# Power.net
KiCad netlist of a schematic drawn in Altium Designer
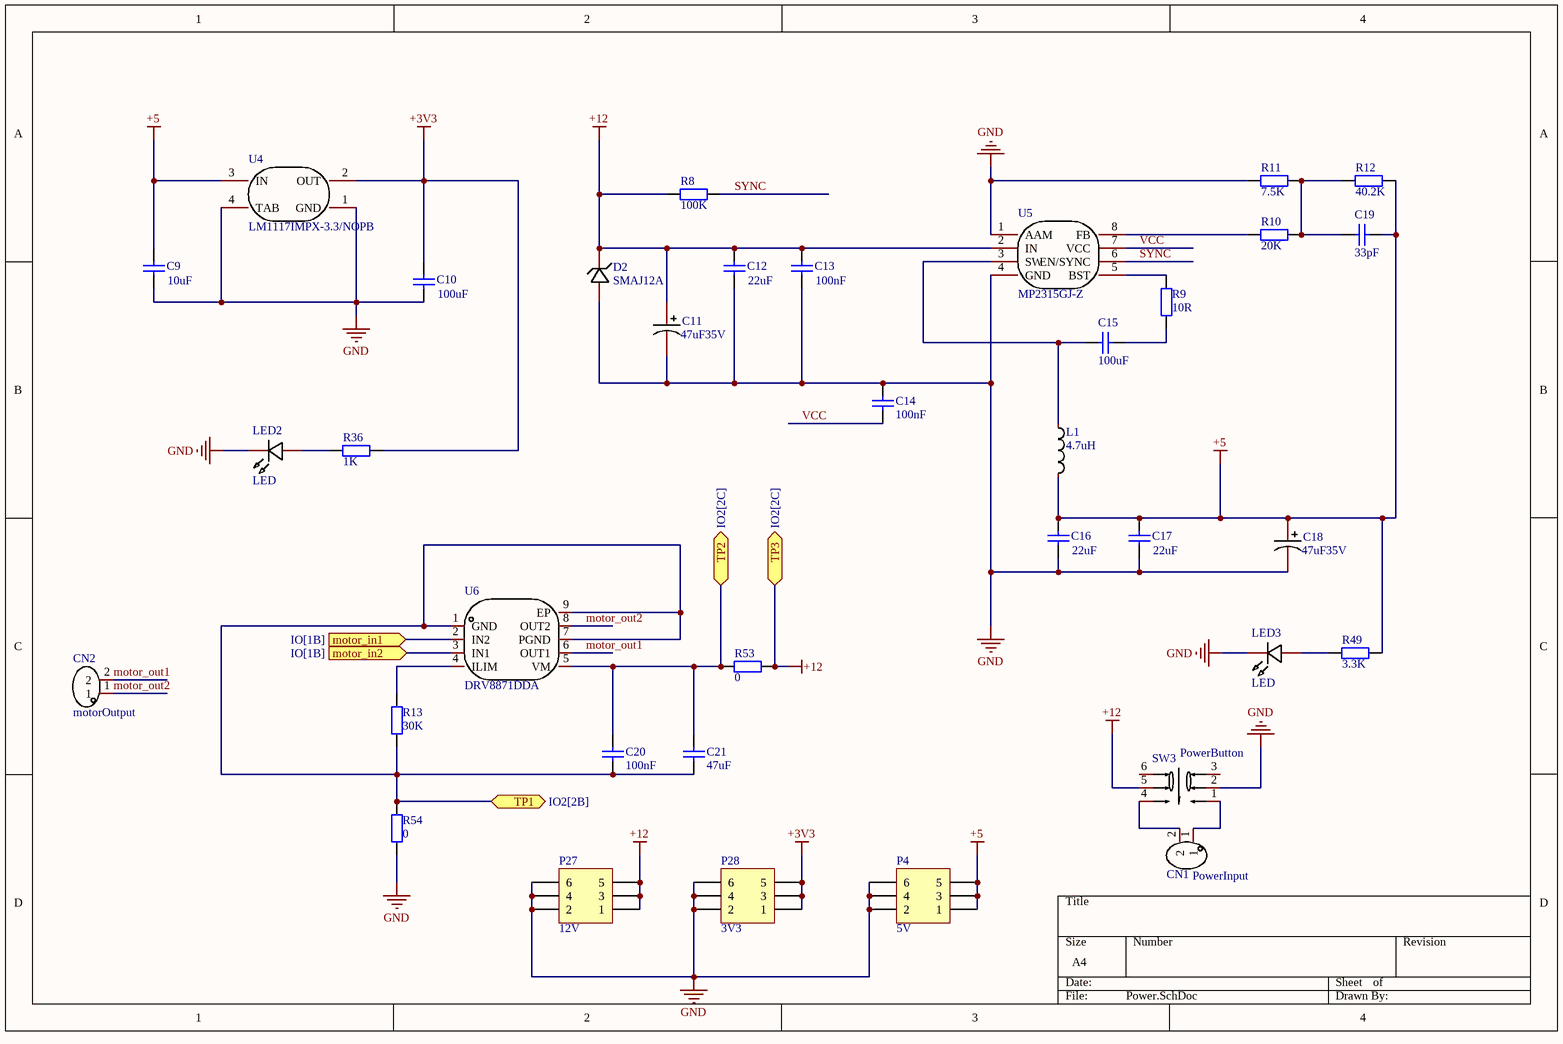
[diagram p0: Power.SchDoc]

(export (version "E")
  (design (tool "Eeschema 10.0.6"))
  (components
    (comp (ref "C9")
      (value "10uF")
      (footprint "RAD-0.3")
      (description "Capacitor")
      (fields (field (name "Comment") "Cap") (field (name "PUBLISHER") "Altium Limited"))
      (libsource (lib "Miscellaneous Devices") (part "Cap"))
    )
    (comp (ref "C10")
      (value "100uF")
      (footprint "RAD-0.3")
      (description "Capacitor")
      (fields (field (name "Comment") "Cap") (field (name "PUBLISHER") "Altium Limited"))
      (libsource (lib "Miscellaneous Devices") (part "Cap"))
    )
    (comp (ref "C11")
      (value "47uF")
      (footprint "CAP-TH_BD5.0-P2.00-D0.5-FD-A")
      (fields
        (field (name "MANUFACTURER") "KNSCHA(科尼盛)")
        (field (name "MANUFACTURER PART") "01EC1119")
        (field (name "TOLERANCE") "±20%")
        (field (name "NAME") "47uF35V")
      )
      (libsource (lib "47uF35V") (part "01EC1119"))
    )
    (comp (ref "C12")
      (value "22uF")
      (footprint "RAD-0.3")
      (description "Capacitor")
      (fields (field (name "Comment") "Cap") (field (name "PUBLISHER") "Altium Limited"))
      (libsource (lib "Miscellaneous Devices") (part "Cap"))
    )
    (comp (ref "C13")
      (value "100nF")
      (footprint "RAD-0.3")
      (description "Capacitor")
      (fields (field (name "Comment") "Cap") (field (name "PUBLISHER") "Altium Limited"))
      (libsource (lib "Miscellaneous Devices") (part "Cap"))
    )
    (comp (ref "C14")
      (value "100nF")
      (footprint "RAD-0.3")
      (description "Capacitor")
      (fields (field (name "Comment") "Cap") (field (name "PUBLISHER") "Altium Limited"))
      (libsource (lib "Miscellaneous Devices") (part "Cap"))
    )
    (comp (ref "C15")
      (value "100uF")
      (footprint "RAD-0.3")
      (description "Capacitor")
      (fields (field (name "Comment") "Cap") (field (name "PUBLISHER") "Altium Limited"))
      (libsource (lib "Miscellaneous Devices") (part "Cap"))
    )
    (comp (ref "C16")
      (value "22uF")
      (footprint "RAD-0.3")
      (description "Capacitor")
      (fields (field (name "Comment") "Cap") (field (name "PUBLISHER") "Altium Limited"))
      (libsource (lib "Miscellaneous Devices") (part "Cap"))
    )
    (comp (ref "C17")
      (value "22uF")
      (footprint "RAD-0.3")
      (description "Capacitor")
      (fields (field (name "Comment") "Cap") (field (name "PUBLISHER") "Altium Limited"))
      (libsource (lib "Miscellaneous Devices") (part "Cap"))
    )
    (comp (ref "C18")
      (value "47uF")
      (footprint "CAP-TH_BD5.0-P2.00-D0.5-FD-A")
      (fields
        (field (name "MANUFACTURER") "KNSCHA(科尼盛)")
        (field (name "MANUFACTURER PART") "01EC1119")
        (field (name "TOLERANCE") "±20%")
        (field (name "NAME") "47uF35V")
      )
      (libsource (lib "47uF35V") (part "01EC1119"))
    )
    (comp (ref "C19")
      (value "33pF")
      (footprint "RAD-0.3")
      (description "Capacitor")
      (fields (field (name "Comment") "Cap") (field (name "PUBLISHER") "Altium Limited"))
      (libsource (lib "Miscellaneous Devices") (part "Cap"))
    )
    (comp (ref "C20")
      (value "100nF")
      (footprint "RAD-0.3")
      (description "Capacitor")
      (fields (field (name "Comment") "Cap") (field (name "PUBLISHER") "Altium Limited"))
      (libsource (lib "Miscellaneous Devices") (part "Cap"))
    )
    (comp (ref "C21")
      (value "47uF")
      (footprint "RAD-0.3")
      (description "Capacitor")
      (fields (field (name "Comment") "Cap") (field (name "PUBLISHER") "Altium Limited"))
      (libsource (lib "Miscellaneous Devices") (part "Cap"))
    )
    (comp (ref "CN1")
      (value "MX126-5.0-02P-GN01-Cu-S-A")
      (footprint "CONN-TH_2P-P5.00_MX126-5.0-GN01-02P-CU-S-A")
      (fields (field (name "MANUFACTURER") "MAX(迈旭)") (field (name "MX126-5.0-02P-GN01-CU-S-A") "PowerInput"))
      (libsource (lib "MX126-5.0-02P-GN01-Cu-S-A") (part "MX126-5.0-02P-GN01-Cu-S-A"))
    )
    (comp (ref "CN2")
      (value "MX126-5.0-02P-GN01-Cu-S-A")
      (footprint "CONN-TH_2P-P5.00_MX126-5.0-GN01-02P-CU-S-A")
      (fields
        (field (name "MANUFACTURER") "MAX(迈旭)")
        (field (name "MX126-5.0-02P-GN01-CU-S-A") "motorOutput")
      )
      (libsource (lib "MX126-5.0-02P-GN01-Cu-S-A") (part "MX126-5.0-02P-GN01-Cu-S-A"))
    )
    (comp (ref "D2")
      (value "SMAJ12A")
      (footprint "SMA_L4.3-W2.6-LS5.2-RD")
      (fields (field (name "MANUFACTURER") "Littelfuse(美国力特)") (field (name "NAME") "SMAJ12A"))
      (libsource (lib "SMAJ12A") (part "SMAJ12A_C148213"))
    )
    (comp (ref "L1")
      (value "4.7uH")
      (footprint "IND-SMD_L5.4-W5.2_FXL0530")
      (fields
        (field (name "MANUFACTURER") "cjiang(长江微电)")
        (field (name "MANUFACTURER PART") "FXL0530-4R7-M")
        (field (name "TOLERANCE") "±20%")
        (field (name "4R7") "4.7uH")
      )
      (libsource (lib "4R7") (part "FXL0530-4R7-M"))
    )
    (comp (ref "LED2")
      (value "HL-503S45FC")
      (footprint "LED-TH_BD5.0-P2.54-FD")
      (fields (field (name "MANUFACTURER") "HONGLITRONIC(鸿利光电)") (field (name "NAME") "LED"))
      (libsource (lib "LED") (part "HL-503S45FC"))
    )
    (comp (ref "LED3")
      (value "HL-503S45FC")
      (footprint "LED-TH_BD5.0-P2.54-FD")
      (fields (field (name "MANUFACTURER") "HONGLITRONIC(鸿利光电)") (field (name "NAME") "LED"))
      (libsource (lib "LED") (part "HL-503S45FC"))
    )
    (comp (ref "P4")
      (value "5V")
      (footprint "HDR2X3")
      (description "Header, 3-Pin, Dual row")
      (fields (field (name "PUBLISHER") "Altium Limited"))
      (libsource (lib "Miscellaneous Connectors") (part "Header 3X2"))
    )
    (comp (ref "P27")
      (value "12V")
      (footprint "HDR2X3")
      (description "Header, 3-Pin, Dual row")
      (fields (field (name "PUBLISHER") "Altium Limited"))
      (libsource (lib "Miscellaneous Connectors") (part "Header 3X2"))
    )
    (comp (ref "P28")
      (value "3V3")
      (footprint "HDR2X3")
      (description "Header, 3-Pin, Dual row")
      (fields (field (name "PUBLISHER") "Altium Limited"))
      (libsource (lib "Miscellaneous Connectors") (part "Header 3X2"))
    )
    (comp (ref "R8")
      (value "100K")
      (footprint "AXIAL-0.4")
      (description "Resistor")
      (fields (field (name "Comment") "Res2") (field (name "PUBLISHER") "Altium Limited"))
      (libsource (lib "") (part "Res2_3"))
    )
    (comp (ref "R9")
      (value "10R")
      (footprint "AXIAL-0.4")
      (description "Resistor")
      (fields (field (name "Comment") "Res2") (field (name "PUBLISHER") "Altium Limited"))
      (libsource (lib "") (part "Res2_2"))
    )
    (comp (ref "R10")
      (value "20K")
      (footprint "AXIAL-0.4")
      (description "Resistor")
      (fields (field (name "Comment") "Res2") (field (name "PUBLISHER") "Altium Limited"))
      (libsource (lib "Miscellaneous Devices") (part "Res2"))
    )
    (comp (ref "R11")
      (value "7.5K")
      (footprint "AXIAL-0.4")
      (description "Resistor")
      (fields (field (name "Comment") "Res2") (field (name "PUBLISHER") "Altium Limited"))
      (libsource (lib "Miscellaneous Devices") (part "Res2"))
    )
    (comp (ref "R12")
      (value "40.2K")
      (footprint "AXIAL-0.4")
      (description "Resistor")
      (fields (field (name "Comment") "Res2") (field (name "PUBLISHER") "Altium Limited"))
      (libsource (lib "Miscellaneous Devices") (part "Res2"))
    )
    (comp (ref "R13")
      (value "30K")
      (footprint "AXIAL-0.4")
      (description "Resistor")
      (fields (field (name "Comment") "Res2") (field (name "PUBLISHER") "Altium Limited"))
      (libsource (lib "") (part "Res2_2"))
    )
    (comp (ref "R36")
      (value "1K")
      (footprint "AXIAL-0.4")
      (description "Resistor")
      (fields (field (name "Comment") "Res2") (field (name "PUBLISHER") "Altium Limited"))
      (libsource (lib "") (part "Res2_3"))
    )
    (comp (ref "R49")
      (value "3.3K")
      (footprint "AXIAL-0.4")
      (description "Resistor")
      (fields (field (name "Comment") "Res2") (field (name "PUBLISHER") "Altium Limited"))
      (libsource (lib "") (part "Res2_3"))
    )
    (comp (ref "R53")
      (value "0")
      (footprint "AXIAL-0.4")
      (description "Resistor")
      (fields (field (name "Comment") "Res2") (field (name "PUBLISHER") "Altium Limited"))
      (libsource (lib "Miscellaneous Devices") (part "Res2"))
    )
    (comp (ref "R54")
      (value "0")
      (footprint "AXIAL-0.4")
      (description "Resistor")
      (fields (field (name "Comment") "Res2") (field (name "PUBLISHER") "Altium Limited"))
      (libsource (lib "") (part "Res2_1"))
    )
    (comp (ref "SW3")
      (value "XKB7070-Z")
      (footprint "SW-TH_6P-L7.0-W7.0-P2.00")
      (fields (field (name "MANUFACTURER") "XKB Connectivity(中国星坤)") (field (name "XKB7070-Z") "PowerButton"))
      (libsource (lib "XKB7070-Z") (part "XKB7070-Z"))
    )
    (comp (ref "U4")
      (value "LM1117IMPX-3.3/NOPB")
      (footprint "SOT-223_L6.5-W3.5-P2.30-LS7.0-BR")
      (fields (field (name "MANUFACTURER") "TI(德州仪器)") (field (name "NAME") "LM1117IMPX-3.3/NOPB"))
      (libsource (lib "LM1117") (part "LM1117IMPX-3.3/NOPB"))
    )
    (comp (ref "U5")
      (value "MP2315GJ-Z")
      (footprint "TSOT-23-8_L2.9-W1.6-P0.65-LS2.8-BR")
      (fields (field (name "MANUFACTURER") "MPS(芯源)") (field (name "NAME") "MP2315GJ-Z"))
      (libsource (lib "MP2315") (part "MP2315GJ-Z"))
    )
    (comp (ref "U6")
      (value "DRV8871DDA")
      (footprint "POWERPAD-SO-8_L4.9-W3.9-P1.27-LS6.0-BL-EP")
      (fields (field (name "MANUFACTURER") "TI(德州仪器)") (field (name "NAME") "DRV8871DDA"))
      (libsource (lib "DRV8871") (part "DRV8871DDA"))
    )
  )
  (nets
    (net (code "1") (name "+3V3") (class "Default")
      (node (ref "C10") (pin "2") (pinfunction "2_2") (pintype "passive"))
      (node (ref "P28") (pin "1") (pinfunction "1_1") (pintype "passive"))
      (node (ref "P28") (pin "3") (pinfunction "3_3") (pintype "passive"))
      (node (ref "P28") (pin "5") (pinfunction "5_5") (pintype "passive"))
      (node (ref "R36") (pin "1") (pinfunction "1_1") (pintype "passive"))
      (node (ref "U4") (pin "2") (pinfunction "OUT_2") (pintype "passive"))
    )
    (net (code "2") (name "+5") (class "Default")
      (node (ref "C16") (pin "2") (pinfunction "2_2") (pintype "passive"))
      (node (ref "C17") (pin "2") (pinfunction "2_2") (pintype "passive"))
      (node (ref "C18") (pin "1") (pinfunction "1_1") (pintype "passive"))
      (node (ref "C19") (pin "2") (pinfunction "2_2") (pintype "passive"))
      (node (ref "C9") (pin "2") (pinfunction "2_2") (pintype "passive"))
      (node (ref "L1") (pin "2") (pinfunction "2_2") (pintype "passive"))
      (node (ref "P4") (pin "1") (pinfunction "1_1") (pintype "passive"))
      (node (ref "P4") (pin "3") (pinfunction "3_3") (pintype "passive"))
      (node (ref "P4") (pin "5") (pinfunction "5_5") (pintype "passive"))
      (node (ref "R12") (pin "2") (pinfunction "2_2") (pintype "passive"))
      (node (ref "R49") (pin "1") (pinfunction "1_1") (pintype "passive"))
      (node (ref "U4") (pin "3") (pinfunction "IN_3") (pintype "passive"))
    )
    (net (code "3") (name "+12") (class "Default")
      (node (ref "C11") (pin "1") (pinfunction "1_1") (pintype "passive"))
      (node (ref "C12") (pin "2") (pinfunction "2_2") (pintype "passive"))
      (node (ref "C13") (pin "2") (pinfunction "2_2") (pintype "passive"))
      (node (ref "D2") (pin "1") (pinfunction "C_1") (pintype "passive"))
      (node (ref "P27") (pin "1") (pinfunction "1_1") (pintype "passive"))
      (node (ref "P27") (pin "3") (pinfunction "3_3") (pintype "passive"))
      (node (ref "P27") (pin "5") (pinfunction "5_5") (pintype "passive"))
      (node (ref "R53") (pin "2") (pinfunction "2_2") (pintype "passive"))
      (node (ref "R8") (pin "2") (pinfunction "2_2") (pintype "passive"))
      (node (ref "SW3") (pin "5") (pinfunction "5_5") (pintype "passive"))
      (node (ref "U5") (pin "2") (pinfunction "IN_2") (pintype "passive"))
    )
    (net (code "4") (name "/SYNC") (class "Default")
      (node (ref "R8") (pin "1") (pinfunction "1_1") (pintype "passive"))
      (node (ref "U5") (pin "6") (pinfunction "EN/SYNC_6") (pintype "passive"))
    )
    (net (code "5") (name "/TP1") (class "Default")
      (node (ref "C20") (pin "2") (pinfunction "2_2") (pintype "passive"))
      (node (ref "C21") (pin "2") (pinfunction "2_2") (pintype "passive"))
      (node (ref "R13") (pin "2") (pinfunction "2_2") (pintype "passive"))
      (node (ref "R54") (pin "2") (pinfunction "2_2") (pintype "passive"))
      (node (ref "U6") (pin "1") (pinfunction "GND_1") (pintype "passive"))
      (node (ref "U6") (pin "7") (pinfunction "PGND_7") (pintype "passive"))
      (node (ref "U6") (pin "9") (pinfunction "EP_9") (pintype "passive"))
    )
    (net (code "6") (name "/TP2") (class "Default")
      (node (ref "C20") (pin "1") (pinfunction "1_1") (pintype "passive"))
      (node (ref "C21") (pin "1") (pinfunction "1_1") (pintype "passive"))
      (node (ref "R53") (pin "1") (pinfunction "1_1") (pintype "passive"))
      (node (ref "U6") (pin "5") (pinfunction "VM_5") (pintype "passive"))
    )
    (net (code "7") (name "/VCC") (class "Default")
      (node (ref "C14") (pin "2") (pinfunction "2_2") (pintype "passive"))
      (node (ref "U5") (pin "7") (pinfunction "VCC_7") (pintype "passive"))
    )
    (net (code "8") (name "/motor_in1") (class "Default")
      (node (ref "U6") (pin "2") (pinfunction "IN2_2") (pintype "passive"))
    )
    (net (code "9") (name "/motor_in2") (class "Default")
      (node (ref "U6") (pin "3") (pinfunction "IN1_3") (pintype "passive"))
    )
    (net (code "10") (name "/motor_out1") (class "Default")
      (node (ref "CN2") (pin "2") (pinfunction "2_2") (pintype "passive"))
      (node (ref "U6") (pin "6") (pinfunction "OUT1_6") (pintype "passive"))
    )
    (net (code "11") (name "/motor_out2") (class "Default")
      (node (ref "CN2") (pin "1") (pinfunction "1_1") (pintype "passive"))
      (node (ref "U6") (pin "8") (pinfunction "OUT2_8") (pintype "passive"))
    )
    (net (code "12") (name "GND") (class "Default")
      (node (ref "C10") (pin "1") (pinfunction "1_1") (pintype "passive"))
      (node (ref "C11") (pin "2") (pinfunction "2_2") (pintype "passive"))
      (node (ref "C12") (pin "1") (pinfunction "1_1") (pintype "passive"))
      (node (ref "C13") (pin "1") (pinfunction "1_1") (pintype "passive"))
      (node (ref "C14") (pin "1") (pinfunction "1_1") (pintype "passive"))
      (node (ref "C16") (pin "1") (pinfunction "1_1") (pintype "passive"))
      (node (ref "C17") (pin "1") (pinfunction "1_1") (pintype "passive"))
      (node (ref "C18") (pin "2") (pinfunction "2_2") (pintype "passive"))
      (node (ref "C9") (pin "1") (pinfunction "1_1") (pintype "passive"))
      (node (ref "D2") (pin "2") (pinfunction "A_2") (pintype "passive"))
      (node (ref "LED2") (pin "2") (pinfunction "2_2") (pintype "passive"))
      (node (ref "LED3") (pin "2") (pinfunction "2_2") (pintype "passive"))
      (node (ref "P27") (pin "2") (pinfunction "2_2") (pintype "passive"))
      (node (ref "P27") (pin "4") (pinfunction "4_4") (pintype "passive"))
      (node (ref "P27") (pin "6") (pinfunction "6_6") (pintype "passive"))
      (node (ref "P28") (pin "2") (pinfunction "2_2") (pintype "passive"))
      (node (ref "P28") (pin "4") (pinfunction "4_4") (pintype "passive"))
      (node (ref "P28") (pin "6") (pinfunction "6_6") (pintype "passive"))
      (node (ref "P4") (pin "2") (pinfunction "2_2") (pintype "passive"))
      (node (ref "P4") (pin "4") (pinfunction "4_4") (pintype "passive"))
      (node (ref "P4") (pin "6") (pinfunction "6_6") (pintype "passive"))
      (node (ref "R11") (pin "1") (pinfunction "1_1") (pintype "passive"))
      (node (ref "R54") (pin "1") (pinfunction "1_1") (pintype "passive"))
      (node (ref "SW3") (pin "2") (pinfunction "2_2") (pintype "passive"))
      (node (ref "U4") (pin "1") (pinfunction "GND_1") (pintype "passive"))
      (node (ref "U4") (pin "4") (pinfunction "TAB_4") (pintype "passive"))
      (node (ref "U5") (pin "1") (pinfunction "AAM_1") (pintype "passive"))
      (node (ref "U5") (pin "4") (pinfunction "GND_4") (pintype "passive"))
    )
    (net (code "13") (name "Net-(C15-Pad2)") (class "Default")
      (node (ref "C15") (pin "2") (pinfunction "2_2") (pintype "passive"))
      (node (ref "R9") (pin "2") (pinfunction "2_2") (pintype "passive"))
    )
    (net (code "14") (name "Net-(C19-Pad1)") (class "Default")
      (node (ref "C19") (pin "1") (pinfunction "1_1") (pintype "passive"))
      (node (ref "R10") (pin "2") (pinfunction "2_2") (pintype "passive"))
      (node (ref "R11") (pin "2") (pinfunction "2_2") (pintype "passive"))
      (node (ref "R12") (pin "1") (pinfunction "1_1") (pintype "passive"))
    )
    (net (code "15") (name "Net-(CN1-Pad1)") (class "Default")
      (node (ref "CN1") (pin "1") (pinfunction "1_1") (pintype "passive"))
      (node (ref "SW3") (pin "1") (pinfunction "1_1") (pintype "passive"))
    )
    (net (code "16") (name "Net-(CN1-Pad2)") (class "Default")
      (node (ref "CN1") (pin "2") (pinfunction "2_2") (pintype "passive"))
      (node (ref "SW3") (pin "4") (pinfunction "4_4") (pintype "passive"))
    )
    (net (code "17") (name "Net-(LED2-Pad1)") (class "Default")
      (node (ref "LED2") (pin "1") (pinfunction "1_1") (pintype "passive"))
      (node (ref "R36") (pin "2") (pinfunction "2_2") (pintype "passive"))
    )
    (net (code "18") (name "Net-(LED3-Pad1)") (class "Default")
      (node (ref "LED3") (pin "1") (pinfunction "1_1") (pintype "passive"))
      (node (ref "R49") (pin "2") (pinfunction "2_2") (pintype "passive"))
    )
    (net (code "19") (name "Net-(U5-BST)") (class "Default")
      (node (ref "R9") (pin "1") (pinfunction "1_1") (pintype "passive"))
      (node (ref "U5") (pin "5") (pinfunction "BST_5") (pintype "passive"))
    )
    (net (code "20") (name "Net-(U5-FB)") (class "Default")
      (node (ref "R10") (pin "1") (pinfunction "1_1") (pintype "passive"))
      (node (ref "U5") (pin "8") (pinfunction "FB_8") (pintype "passive"))
    )
    (net (code "21") (name "Net-(U5-SW)") (class "Default")
      (node (ref "C15") (pin "1") (pinfunction "1_1") (pintype "passive"))
      (node (ref "L1") (pin "1") (pinfunction "1_1") (pintype "passive"))
      (node (ref "U5") (pin "3") (pinfunction "SW_3") (pintype "passive"))
    )
    (net (code "22") (name "Net-(U6-ILIM)") (class "Default")
      (node (ref "R13") (pin "1") (pinfunction "1_1") (pintype "passive"))
      (node (ref "U6") (pin "4") (pinfunction "ILIM_4") (pintype "passive"))
    )
    (net (code "23") (name "unconnected-(SW3-Pad3)") (class "Default")
      (node (ref "SW3") (pin "3") (pinfunction "3_3") (pintype "passive"))
    )
    (net (code "24") (name "unconnected-(SW3-Pad6)") (class "Default")
      (node (ref "SW3") (pin "6") (pinfunction "6_6") (pintype "passive"))
    )
  )
)
